# AD9361.net
KiCad netlist of a schematic drawn in Altium Designer
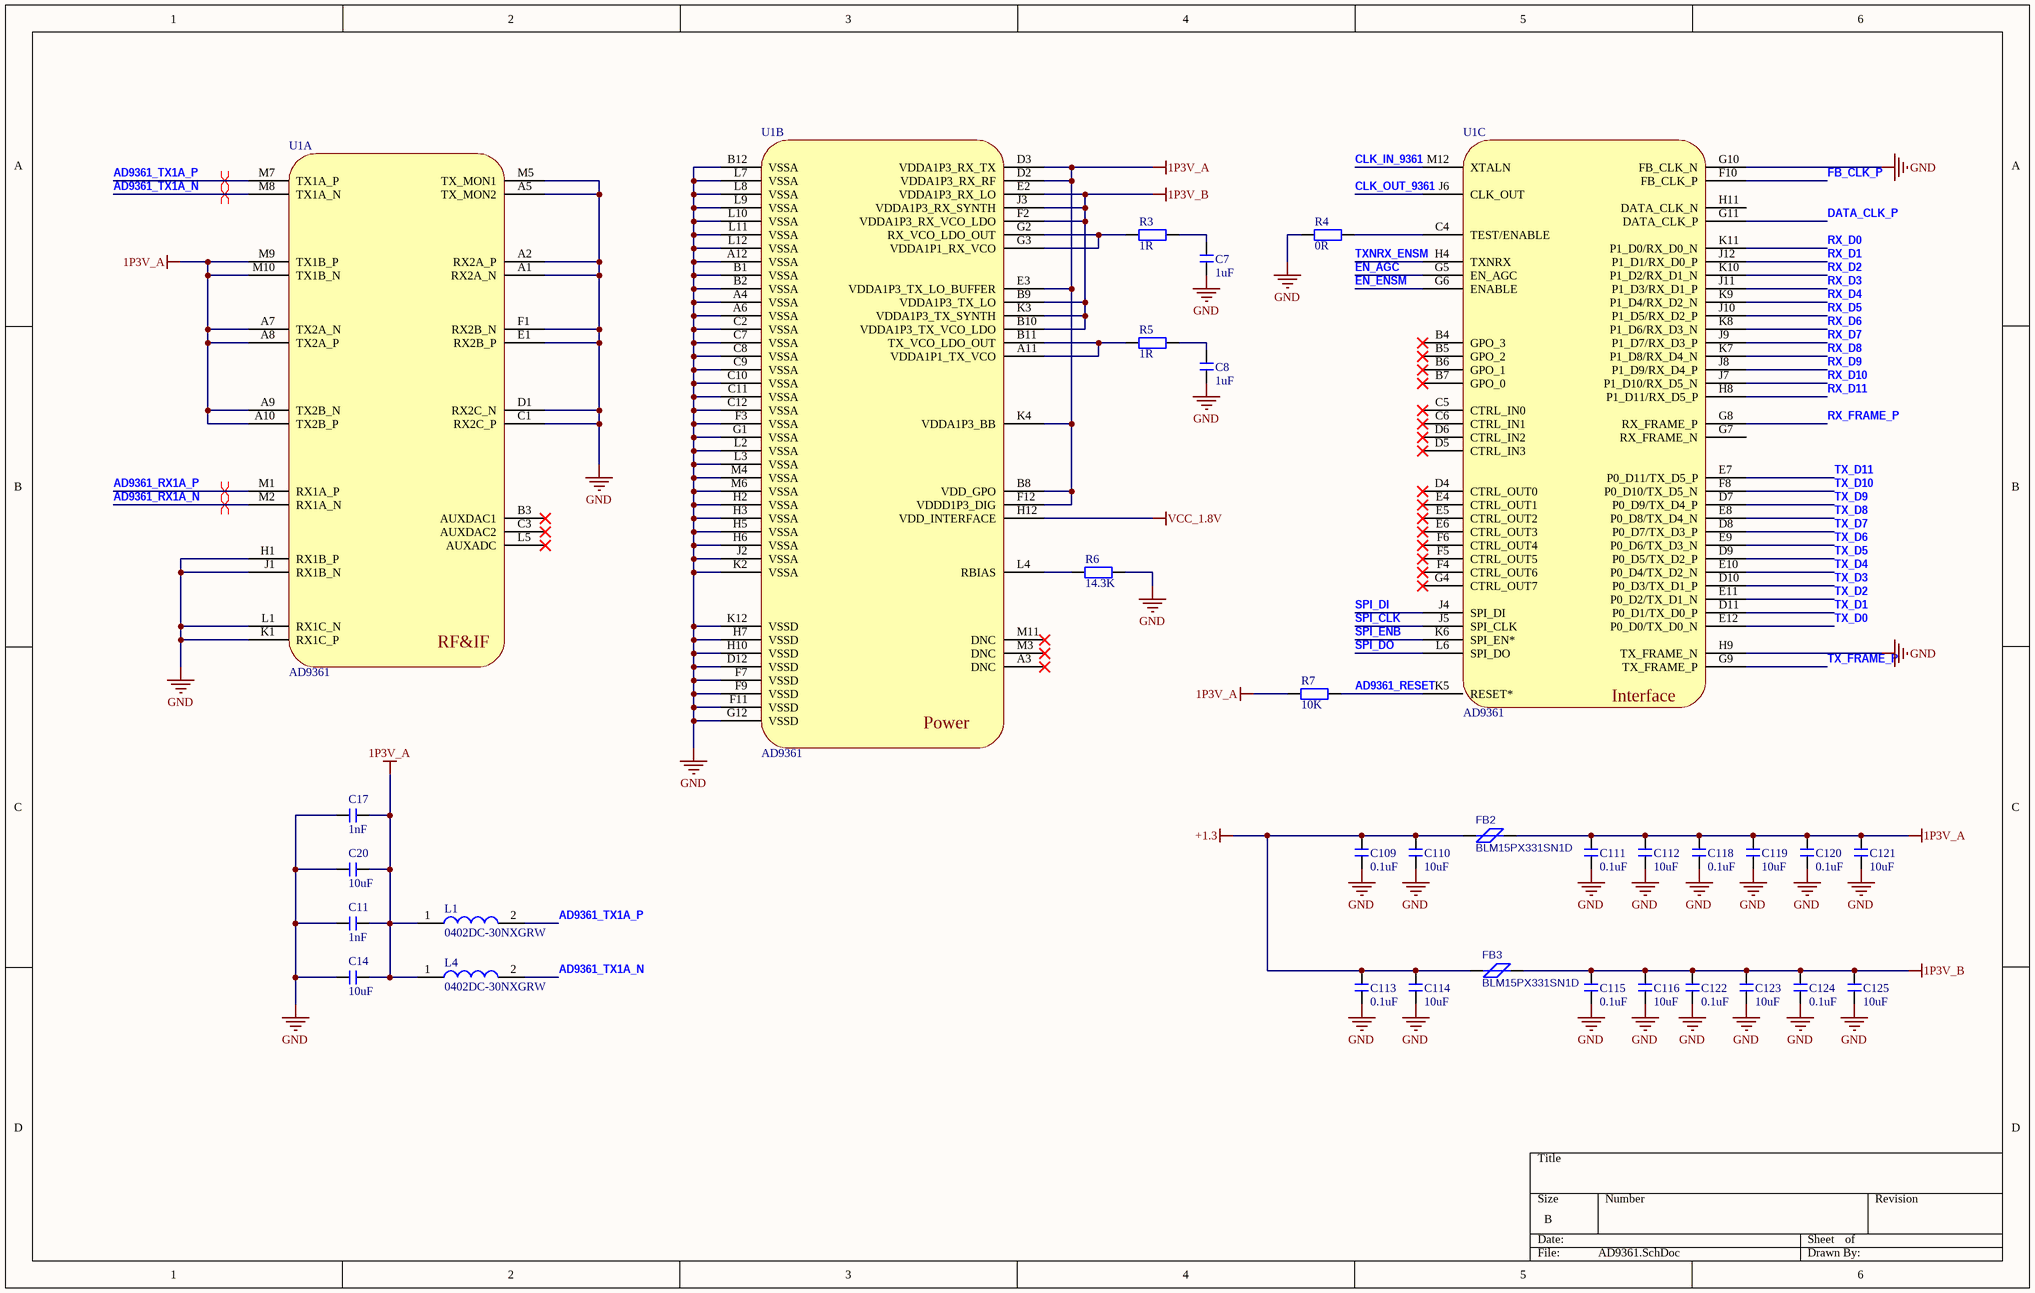
[diagram p0: AD9361.SchDoc]

(export (version "E")
  (design (tool "Eeschema 10.0.6"))
  (components
    (comp (ref "C7")
      (value "1uF")
      (footprint "SamacSys:CAP_0402")
      (description "无极性贴片电容")
      (fields (field (name "版权归属") "源创客"))
      (libsource (lib "源创客") (part "C"))
    )
    (comp (ref "C8")
      (value "1uF")
      (footprint "SamacSys:CAP_0402")
      (description "无极性贴片电容")
      (fields (field (name "版权归属") "源创客"))
      (libsource (lib "源创客") (part "C"))
    )
    (comp (ref "C11")
      (value "1nF")
      (footprint "SamacSys:CAP_0201")
      (description "无极性贴片电容")
      (fields (field (name "版权归属") "源创客"))
      (libsource (lib "源创客") (part "C"))
    )
    (comp (ref "C14")
      (value "10uF")
      (footprint "SamacSys:CAP_0402")
      (description "无极性贴片电容")
      (fields (field (name "版权归属") "源创客"))
      (libsource (lib "源创客") (part "C"))
    )
    (comp (ref "C17")
      (value "1nF")
      (footprint "SamacSys:CAP_0201")
      (description "无极性贴片电容")
      (fields (field (name "版权归属") "源创客"))
      (libsource (lib "源创客") (part "C"))
    )
    (comp (ref "C20")
      (value "10uF")
      (footprint "SamacSys:CAP_0402")
      (description "无极性贴片电容")
      (fields (field (name "版权归属") "源创客"))
      (libsource (lib "源创客") (part "C"))
    )
    (comp (ref "C109")
      (value "0.1uF")
      (footprint "SamacSys:CAP_0402")
      (description "无极性贴片电容")
      (fields (field (name "版权归属") "源创客"))
      (libsource (lib "源创客") (part "C"))
    )
    (comp (ref "C110")
      (value "10uF")
      (footprint "SamacSys:CAP_0402")
      (description "无极性贴片电容")
      (fields (field (name "版权归属") "源创客"))
      (libsource (lib "源创客") (part "C"))
    )
    (comp (ref "C111")
      (value "0.1uF")
      (footprint "SamacSys:CAP_0201")
      (description "无极性贴片电容")
      (fields (field (name "版权归属") "源创客"))
      (libsource (lib "源创客") (part "C"))
    )
    (comp (ref "C112")
      (value "10uF")
      (footprint "SamacSys:CAP_0201")
      (description "无极性贴片电容")
      (fields (field (name "版权归属") "源创客"))
      (libsource (lib "源创客") (part "C"))
    )
    (comp (ref "C113")
      (value "0.1uF")
      (footprint "SamacSys:CAP_0402")
      (description "无极性贴片电容")
      (fields (field (name "版权归属") "源创客"))
      (libsource (lib "源创客") (part "C"))
    )
    (comp (ref "C114")
      (value "10uF")
      (footprint "SamacSys:CAP_0402")
      (description "无极性贴片电容")
      (fields (field (name "版权归属") "源创客"))
      (libsource (lib "源创客") (part "C"))
    )
    (comp (ref "C115")
      (value "0.1uF")
      (footprint "SamacSys:CAP_0201")
      (description "无极性贴片电容")
      (fields (field (name "版权归属") "源创客"))
      (libsource (lib "源创客") (part "C"))
    )
    (comp (ref "C116")
      (value "10uF")
      (footprint "SamacSys:CAP_0201")
      (description "无极性贴片电容")
      (fields (field (name "版权归属") "源创客"))
      (libsource (lib "源创客") (part "C"))
    )
    (comp (ref "C118")
      (value "0.1uF")
      (footprint "SamacSys:CAP_0201")
      (description "无极性贴片电容")
      (fields (field (name "版权归属") "源创客"))
      (libsource (lib "源创客") (part "C"))
    )
    (comp (ref "C119")
      (value "10uF")
      (footprint "SamacSys:CAP_0201")
      (description "无极性贴片电容")
      (fields (field (name "版权归属") "源创客"))
      (libsource (lib "源创客") (part "C"))
    )
    (comp (ref "C120")
      (value "0.1uF")
      (footprint "SamacSys:CAP_0201")
      (description "无极性贴片电容")
      (fields (field (name "版权归属") "源创客"))
      (libsource (lib "源创客") (part "C"))
    )
    (comp (ref "C121")
      (value "10uF")
      (footprint "SamacSys:CAP_0201")
      (description "无极性贴片电容")
      (fields (field (name "版权归属") "源创客"))
      (libsource (lib "源创客") (part "C"))
    )
    (comp (ref "C122")
      (value "0.1uF")
      (footprint "SamacSys:CAP_0201")
      (description "无极性贴片电容")
      (fields (field (name "版权归属") "源创客"))
      (libsource (lib "源创客") (part "C"))
    )
    (comp (ref "C123")
      (value "10uF")
      (footprint "SamacSys:CAP_0201")
      (description "无极性贴片电容")
      (fields (field (name "版权归属") "源创客"))
      (libsource (lib "源创客") (part "C"))
    )
    (comp (ref "C124")
      (value "0.1uF")
      (footprint "SamacSys:CAP_0201")
      (description "无极性贴片电容")
      (fields (field (name "版权归属") "源创客"))
      (libsource (lib "源创客") (part "C"))
    )
    (comp (ref "C125")
      (value "10uF")
      (footprint "SamacSys:CAP_0201")
      (description "无极性贴片电容")
      (fields (field (name "版权归属") "源创客"))
      (libsource (lib "源创客") (part "C"))
    )
    (comp (ref "FB2")
      (value "BLM15PX331SN1D")
      (footprint "0402")
      (fields (field (name "BOM_SUPPLIER PART") "C160975") (field (name "CONTRIBUTOR") "LCSC"))
      (libsource (lib "xc7k160t") (part "BLM15PX331SN1D"))
    )
    (comp (ref "FB3")
      (value "BLM15PX331SN1D")
      (footprint "0402")
      (fields (field (name "BOM_SUPPLIER PART") "C160975") (field (name "CONTRIBUTOR") "LCSC"))
      (libsource (lib "xc7k160t") (part "BLM15PX331SN1D"))
    )
    (comp (ref "L1")
      (value "0402DC-30NXGRW")
      (footprint "0402DC SERIES")
      (description "Inductor")
      (fields
        (field (name "MANUFACTURER_PART_NUMBER") "0402DC-36NXJRW")
        (field (name "MOUSER PART NUMBER") "994-0402DC-36NXJRW")
      )
      (libsource (lib "xc7k160t") (part "0402DC-36NXJRW"))
    )
    (comp (ref "L4")
      (value "0402DC-30NXGRW")
      (footprint "0402DC SERIES")
      (description "Inductor")
      (fields
        (field (name "MANUFACTURER_PART_NUMBER") "0402DC-36NXJRW")
        (field (name "MOUSER PART NUMBER") "994-0402DC-36NXJRW")
      )
      (libsource (lib "xc7k160t") (part "0402DC-36NXJRW"))
    )
    (comp (ref "R3")
      (value "1R")
      (footprint "SamacSys:RES_0201")
      (description "Resistor")
      (libsource (lib "源创客") (part "Resistor"))
    )
    (comp (ref "R4")
      (value "0R")
      (footprint "SamacSys:RES_0201")
      (description "Resistor")
      (libsource (lib "源创客") (part "Resistor"))
    )
    (comp (ref "R5")
      (value "1R")
      (footprint "SamacSys:RES_0201")
      (description "Resistor")
      (libsource (lib "源创客") (part "Resistor"))
    )
    (comp (ref "R6")
      (value "14.3K")
      (footprint "SamacSys:RES_0402")
      (description "Resistor")
      (libsource (lib "源创客") (part "Resistor"))
    )
    (comp (ref "R7")
      (value "10K")
      (footprint "SamacSys:RES_0201")
      (description "Resistor")
      (libsource (lib "源创客") (part "Resistor"))
    )
    (comp (ref "U1") (value "AD9361") (footprint "AD936X") (libsource (lib "xc7k160t") (part "AD9363")))
  )
  (nets
    (net (code "1") (name "+1.3") (class "Default")
      (node (ref "C109") (pin "1") (pinfunction "1_1") (pintype "passive"))
      (node (ref "C110") (pin "2") (pinfunction "2_2") (pintype "passive"))
      (node (ref "C113") (pin "1") (pinfunction "1_1") (pintype "passive"))
      (node (ref "C114") (pin "2") (pinfunction "2_2") (pintype "passive"))
      (node (ref "FB2") (pin "1") (pinfunction "1_1") (pintype "passive"))
      (node (ref "FB3") (pin "1") (pinfunction "1_1") (pintype "passive"))
    )
    (net (code "2") (name "/AD9361_RESET") (class "Default")
      (node (ref "R7") (pin "1") (pinfunction "1_1") (pintype "passive"))
      (node (ref "U1") (pin "K5") (pinfunction "RESET*_K5") (pintype "passive"))
    )
    (net (code "3") (name "/AD9361_RX1A_N") (class "Default")
      (node (ref "U1") (pin "M2") (pinfunction "RX1A_N_M2") (pintype "passive"))
    )
    (net (code "4") (name "/AD9361_RX1A_P") (class "Default")
      (node (ref "U1") (pin "M1") (pinfunction "RX1A_P_M1") (pintype "passive"))
    )
    (net (code "5") (name "/AD9361_TX1A_N") (class "Default")
      (node (ref "L4") (pin "2") (pinfunction "2_2") (pintype "passive"))
      (node (ref "U1") (pin "M8") (pinfunction "TX1A_N_M8") (pintype "passive"))
    )
    (net (code "6") (name "/AD9361_TX1A_P") (class "Default")
      (node (ref "L1") (pin "2") (pinfunction "2_2") (pintype "passive"))
      (node (ref "U1") (pin "M7") (pinfunction "TX1A_P_M7") (pintype "passive"))
    )
    (net (code "7") (name "/CLK_IN_9361") (class "Default")
      (node (ref "U1") (pin "M12") (pinfunction "XTALN_M12") (pintype "passive"))
    )
    (net (code "8") (name "/CLK_OUT_9361") (class "Default")
      (node (ref "U1") (pin "J6") (pinfunction "CLK_OUT_J6") (pintype "passive"))
    )
    (net (code "9") (name "/DATA_CLK_P") (class "Default")
      (node (ref "U1") (pin "G11") (pinfunction "DATA_CLK_P_G11") (pintype "passive"))
    )
    (net (code "10") (name "/EN_AGC") (class "Default")
      (node (ref "U1") (pin "G5") (pinfunction "EN_AGC_G5") (pintype "passive"))
    )
    (net (code "11") (name "/EN_ENSM") (class "Default")
      (node (ref "U1") (pin "G6") (pinfunction "ENABLE_G6") (pintype "passive"))
    )
    (net (code "12") (name "/FB_CLK_P") (class "Default")
      (node (ref "U1") (pin "F10") (pinfunction "FB_CLK_P_F10") (pintype "passive"))
    )
    (net (code "13") (name "/RX_D0") (class "Default")
      (node (ref "U1") (pin "K11") (pinfunction "P1_D0/RX_D0_N_K11") (pintype "passive"))
    )
    (net (code "14") (name "/RX_D1") (class "Default")
      (node (ref "U1") (pin "J12") (pinfunction "P1_D1/RX_D0_P_J12") (pintype "passive"))
    )
    (net (code "15") (name "/RX_D2") (class "Default")
      (node (ref "U1") (pin "K10") (pinfunction "P1_D2/RX_D1_N_K10") (pintype "passive"))
    )
    (net (code "16") (name "/RX_D3") (class "Default")
      (node (ref "U1") (pin "J11") (pinfunction "P1_D3/RX_D1_P_J11") (pintype "passive"))
    )
    (net (code "17") (name "/RX_D4") (class "Default")
      (node (ref "U1") (pin "K9") (pinfunction "P1_D4/RX_D2_N_K9") (pintype "passive"))
    )
    (net (code "18") (name "/RX_D5") (class "Default")
      (node (ref "U1") (pin "J10") (pinfunction "P1_D5/RX_D2_P_J10") (pintype "passive"))
    )
    (net (code "19") (name "/RX_D6") (class "Default")
      (node (ref "U1") (pin "K8") (pinfunction "P1_D6/RX_D3_N_K8") (pintype "passive"))
    )
    (net (code "20") (name "/RX_D7") (class "Default")
      (node (ref "U1") (pin "J9") (pinfunction "P1_D7/RX_D3_P_J9") (pintype "passive"))
    )
    (net (code "21") (name "/RX_D8") (class "Default")
      (node (ref "U1") (pin "K7") (pinfunction "P1_D8/RX_D4_N_K7") (pintype "passive"))
    )
    (net (code "22") (name "/RX_D9") (class "Default")
      (node (ref "U1") (pin "J8") (pinfunction "P1_D9/RX_D4_P_J8") (pintype "passive"))
    )
    (net (code "23") (name "/RX_D10") (class "Default")
      (node (ref "U1") (pin "J7") (pinfunction "P1_D10/RX_D5_N_J7") (pintype "passive"))
    )
    (net (code "24") (name "/RX_D11") (class "Default")
      (node (ref "U1") (pin "H8") (pinfunction "P1_D11/RX_D5_P_H8") (pintype "passive"))
    )
    (net (code "25") (name "/RX_FRAME_P") (class "Default")
      (node (ref "U1") (pin "G8") (pinfunction "RX_FRAME_P_G8") (pintype "passive"))
    )
    (net (code "26") (name "/SPI_CLK") (class "Default")
      (node (ref "U1") (pin "J5") (pinfunction "SPI_CLK_J5") (pintype "passive"))
    )
    (net (code "27") (name "/SPI_DI") (class "Default")
      (node (ref "U1") (pin "J4") (pinfunction "SPI_DI_J4") (pintype "passive"))
    )
    (net (code "28") (name "/SPI_DO") (class "Default")
      (node (ref "U1") (pin "L6") (pinfunction "SPI_DO_L6") (pintype "passive"))
    )
    (net (code "29") (name "/SPI_ENB") (class "Default")
      (node (ref "U1") (pin "K6") (pinfunction "SPI_EN*_K6") (pintype "passive"))
    )
    (net (code "30") (name "/TXNRX_ENSM") (class "Default")
      (node (ref "U1") (pin "H4") (pinfunction "TXNRX_H4") (pintype "passive"))
    )
    (net (code "31") (name "/TX_D0") (class "Default")
      (node (ref "U1") (pin "E12") (pinfunction "P0_D0/TX_D0_N_E12") (pintype "passive"))
    )
    (net (code "32") (name "/TX_D1") (class "Default")
      (node (ref "U1") (pin "D11") (pinfunction "P0_D1/TX_D0_P_D11") (pintype "passive"))
    )
    (net (code "33") (name "/TX_D2") (class "Default")
      (node (ref "U1") (pin "E11") (pinfunction "P0_D2/TX_D1_N_E11") (pintype "passive"))
    )
    (net (code "34") (name "/TX_D3") (class "Default")
      (node (ref "U1") (pin "D10") (pinfunction "P0_D3/TX_D1_P_D10") (pintype "passive"))
    )
    (net (code "35") (name "/TX_D4") (class "Default")
      (node (ref "U1") (pin "E10") (pinfunction "P0_D4/TX_D2_N_E10") (pintype "passive"))
    )
    (net (code "36") (name "/TX_D5") (class "Default")
      (node (ref "U1") (pin "D9") (pinfunction "P0_D5/TX_D2_P_D9") (pintype "passive"))
    )
    (net (code "37") (name "/TX_D6") (class "Default")
      (node (ref "U1") (pin "E9") (pinfunction "P0_D6/TX_D3_N_E9") (pintype "passive"))
    )
    (net (code "38") (name "/TX_D7") (class "Default")
      (node (ref "U1") (pin "D8") (pinfunction "P0_D7/TX_D3_P_D8") (pintype "passive"))
    )
    (net (code "39") (name "/TX_D8") (class "Default")
      (node (ref "U1") (pin "E8") (pinfunction "P0_D8/TX_D4_N_E8") (pintype "passive"))
    )
    (net (code "40") (name "/TX_D9") (class "Default")
      (node (ref "U1") (pin "D7") (pinfunction "P0_D9/TX_D4_P_D7") (pintype "passive"))
    )
    (net (code "41") (name "/TX_D10") (class "Default")
      (node (ref "U1") (pin "F8") (pinfunction "P0_D10/TX_D5_N_F8") (pintype "passive"))
    )
    (net (code "42") (name "/TX_D11") (class "Default")
      (node (ref "U1") (pin "E7") (pinfunction "P0_D11/TX_D5_P_E7") (pintype "passive"))
    )
    (net (code "43") (name "/TX_FRAME_P") (class "Default")
      (node (ref "U1") (pin "G9") (pinfunction "TX_FRAME_P_G9") (pintype "passive"))
    )
    (net (code "44") (name "1P3V_A") (class "Default")
      (node (ref "C11") (pin "2") (pinfunction "2_2") (pintype "passive"))
      (node (ref "C111") (pin "1") (pinfunction "1_1") (pintype "passive"))
      (node (ref "C112") (pin "2") (pinfunction "2_2") (pintype "passive"))
      (node (ref "C118") (pin "1") (pinfunction "1_1") (pintype "passive"))
      (node (ref "C119") (pin "2") (pinfunction "2_2") (pintype "passive"))
      (node (ref "C120") (pin "1") (pinfunction "1_1") (pintype "passive"))
      (node (ref "C121") (pin "2") (pinfunction "2_2") (pintype "passive"))
      (node (ref "C14") (pin "2") (pinfunction "2_2") (pintype "passive"))
      (node (ref "C17") (pin "2") (pinfunction "2_2") (pintype "passive"))
      (node (ref "C20") (pin "2") (pinfunction "2_2") (pintype "passive"))
      (node (ref "FB2") (pin "2") (pinfunction "2_2") (pintype "passive"))
      (node (ref "L1") (pin "1") (pinfunction "1_1") (pintype "passive"))
      (node (ref "L4") (pin "1") (pinfunction "1_1") (pintype "passive"))
      (node (ref "R7") (pin "2") (pinfunction "2_2") (pintype "passive"))
      (node (ref "U1") (pin "A10") (pinfunction "TX2B_P_A10") (pintype "passive"))
      (node (ref "U1") (pin "A7") (pinfunction "TX2A_N_A7") (pintype "passive"))
      (node (ref "U1") (pin "A8") (pinfunction "TX2A_P_A8") (pintype "passive"))
      (node (ref "U1") (pin "A9") (pinfunction "TX2B_N_A9") (pintype "passive"))
      (node (ref "U1") (pin "B8") (pinfunction "VDD_GPO_B8") (pintype "passive"))
      (node (ref "U1") (pin "D2") (pinfunction "VDDA1P3_RX_RF_D2") (pintype "passive"))
      (node (ref "U1") (pin "D3") (pinfunction "VDDA1P3_RX_TX_D3") (pintype "passive"))
      (node (ref "U1") (pin "E3") (pinfunction "VDDA1P3_TX_LO_BUFFER_E3") (pintype "passive"))
      (node (ref "U1") (pin "F12") (pinfunction "VDDD1P3_DIG_F12") (pintype "passive"))
      (node (ref "U1") (pin "K4") (pinfunction "VDDA1P3_BB_K4") (pintype "passive"))
      (node (ref "U1") (pin "M10") (pinfunction "TX1B_N_M10") (pintype "passive"))
      (node (ref "U1") (pin "M9") (pinfunction "TX1B_P_M9") (pintype "passive"))
    )
    (net (code "45") (name "1P3V_B") (class "Default")
      (node (ref "C115") (pin "1") (pinfunction "1_1") (pintype "passive"))
      (node (ref "C116") (pin "2") (pinfunction "2_2") (pintype "passive"))
      (node (ref "C122") (pin "1") (pinfunction "1_1") (pintype "passive"))
      (node (ref "C123") (pin "2") (pinfunction "2_2") (pintype "passive"))
      (node (ref "C124") (pin "1") (pinfunction "1_1") (pintype "passive"))
      (node (ref "C125") (pin "2") (pinfunction "2_2") (pintype "passive"))
      (node (ref "FB3") (pin "2") (pinfunction "2_2") (pintype "passive"))
      (node (ref "U1") (pin "B10") (pinfunction "VDDA1P3_TX_VCO_LDO_B10") (pintype "passive"))
      (node (ref "U1") (pin "B9") (pinfunction "VDDA1P3_TX_LO_B9") (pintype "passive"))
      (node (ref "U1") (pin "E2") (pinfunction "VDDA1P3_RX_LO_E2") (pintype "passive"))
      (node (ref "U1") (pin "F2") (pinfunction "VDDA1P3_RX_VCO_LDO_F2") (pintype "passive"))
      (node (ref "U1") (pin "J3") (pinfunction "VDDA1P3_RX_SYNTH_J3") (pintype "passive"))
      (node (ref "U1") (pin "K3") (pinfunction "VDDA1P3_TX_SYNTH_K3") (pintype "passive"))
    )
    (net (code "46") (name "GND") (class "Default")
      (node (ref "C109") (pin "2") (pinfunction "2_2") (pintype "passive"))
      (node (ref "C11") (pin "1") (pinfunction "1_1") (pintype "passive"))
      (node (ref "C110") (pin "1") (pinfunction "1_1") (pintype "passive"))
      (node (ref "C111") (pin "2") (pinfunction "2_2") (pintype "passive"))
      (node (ref "C112") (pin "1") (pinfunction "1_1") (pintype "passive"))
      (node (ref "C113") (pin "2") (pinfunction "2_2") (pintype "passive"))
      (node (ref "C114") (pin "1") (pinfunction "1_1") (pintype "passive"))
      (node (ref "C115") (pin "2") (pinfunction "2_2") (pintype "passive"))
      (node (ref "C116") (pin "1") (pinfunction "1_1") (pintype "passive"))
      (node (ref "C118") (pin "2") (pinfunction "2_2") (pintype "passive"))
      (node (ref "C119") (pin "1") (pinfunction "1_1") (pintype "passive"))
      (node (ref "C120") (pin "2") (pinfunction "2_2") (pintype "passive"))
      (node (ref "C121") (pin "1") (pinfunction "1_1") (pintype "passive"))
      (node (ref "C122") (pin "2") (pinfunction "2_2") (pintype "passive"))
      (node (ref "C123") (pin "1") (pinfunction "1_1") (pintype "passive"))
      (node (ref "C124") (pin "2") (pinfunction "2_2") (pintype "passive"))
      (node (ref "C125") (pin "1") (pinfunction "1_1") (pintype "passive"))
      (node (ref "C14") (pin "1") (pinfunction "1_1") (pintype "passive"))
      (node (ref "C17") (pin "1") (pinfunction "1_1") (pintype "passive"))
      (node (ref "C20") (pin "1") (pinfunction "1_1") (pintype "passive"))
      (node (ref "C7") (pin "1") (pinfunction "1_1") (pintype "passive"))
      (node (ref "C8") (pin "1") (pinfunction "1_1") (pintype "passive"))
      (node (ref "R4") (pin "2") (pinfunction "2_2") (pintype "passive"))
      (node (ref "R6") (pin "1") (pinfunction "1_1") (pintype "passive"))
      (node (ref "U1") (pin "A1") (pinfunction "RX2A_N_A1") (pintype "passive"))
      (node (ref "U1") (pin "A12") (pinfunction "VSSA_A12") (pintype "passive"))
      (node (ref "U1") (pin "A2") (pinfunction "RX2A_P_A2") (pintype "passive"))
      (node (ref "U1") (pin "A4") (pinfunction "VSSA_A4") (pintype "passive"))
      (node (ref "U1") (pin "A5") (pinfunction "TX_MON2_A5") (pintype "passive"))
      (node (ref "U1") (pin "A6") (pinfunction "VSSA_A6") (pintype "passive"))
      (node (ref "U1") (pin "B1") (pinfunction "VSSA_B1") (pintype "passive"))
      (node (ref "U1") (pin "B12") (pinfunction "VSSA_B12") (pintype "passive"))
      (node (ref "U1") (pin "B2") (pinfunction "VSSA_B2") (pintype "passive"))
      (node (ref "U1") (pin "C1") (pinfunction "RX2C_P_C1") (pintype "passive"))
      (node (ref "U1") (pin "C10") (pinfunction "VSSA_C10") (pintype "passive"))
      (node (ref "U1") (pin "C11") (pinfunction "VSSA_C11") (pintype "passive"))
      (node (ref "U1") (pin "C12") (pinfunction "VSSA_C12") (pintype "passive"))
      (node (ref "U1") (pin "C2") (pinfunction "VSSA_C2") (pintype "passive"))
      (node (ref "U1") (pin "C7") (pinfunction "VSSA_C7") (pintype "passive"))
      (node (ref "U1") (pin "C8") (pinfunction "VSSA_C8") (pintype "passive"))
      (node (ref "U1") (pin "C9") (pinfunction "VSSA_C9") (pintype "passive"))
      (node (ref "U1") (pin "D1") (pinfunction "RX2C_N_D1") (pintype "passive"))
      (node (ref "U1") (pin "D12") (pinfunction "VSSD_D12") (pintype "passive"))
      (node (ref "U1") (pin "E1") (pinfunction "RX2B_P_E1") (pintype "passive"))
      (node (ref "U1") (pin "F1") (pinfunction "RX2B_N_F1") (pintype "passive"))
      (node (ref "U1") (pin "F11") (pinfunction "VSSD_F11") (pintype "passive"))
      (node (ref "U1") (pin "F3") (pinfunction "VSSA_F3") (pintype "passive"))
      (node (ref "U1") (pin "F7") (pinfunction "VSSD_F7") (pintype "passive"))
      (node (ref "U1") (pin "F9") (pinfunction "VSSD_F9") (pintype "passive"))
      (node (ref "U1") (pin "G1") (pinfunction "VSSA_G1") (pintype "passive"))
      (node (ref "U1") (pin "G10") (pinfunction "FB_CLK_N_G10") (pintype "passive"))
      (node (ref "U1") (pin "G12") (pinfunction "VSSD_G12") (pintype "passive"))
      (node (ref "U1") (pin "H1") (pinfunction "RX1B_P_H1") (pintype "passive"))
      (node (ref "U1") (pin "H10") (pinfunction "VSSD_H10") (pintype "passive"))
      (node (ref "U1") (pin "H2") (pinfunction "VSSA_H2") (pintype "passive"))
      (node (ref "U1") (pin "H3") (pinfunction "VSSA_H3") (pintype "passive"))
      (node (ref "U1") (pin "H5") (pinfunction "VSSA_H5") (pintype "passive"))
      (node (ref "U1") (pin "H6") (pinfunction "VSSA_H6") (pintype "passive"))
      (node (ref "U1") (pin "H7") (pinfunction "VSSD_H7") (pintype "passive"))
      (node (ref "U1") (pin "H9") (pinfunction "TX_FRAME_N_H9") (pintype "passive"))
      (node (ref "U1") (pin "J1") (pinfunction "RX1B_N_J1") (pintype "passive"))
      (node (ref "U1") (pin "J2") (pinfunction "VSSA_J2") (pintype "passive"))
      (node (ref "U1") (pin "K1") (pinfunction "RX1C_P_K1") (pintype "passive"))
      (node (ref "U1") (pin "K12") (pinfunction "VSSD_K12") (pintype "passive"))
      (node (ref "U1") (pin "K2") (pinfunction "VSSA_K2") (pintype "passive"))
      (node (ref "U1") (pin "L1") (pinfunction "RX1C_N_L1") (pintype "passive"))
      (node (ref "U1") (pin "L10") (pinfunction "VSSA_L10") (pintype "passive"))
      (node (ref "U1") (pin "L11") (pinfunction "VSSA_L11") (pintype "passive"))
      (node (ref "U1") (pin "L12") (pinfunction "VSSA_L12") (pintype "passive"))
      (node (ref "U1") (pin "L2") (pinfunction "VSSA_L2") (pintype "passive"))
      (node (ref "U1") (pin "L3") (pinfunction "VSSA_L3") (pintype "passive"))
      (node (ref "U1") (pin "L7") (pinfunction "VSSA_L7") (pintype "passive"))
      (node (ref "U1") (pin "L8") (pinfunction "VSSA_L8") (pintype "passive"))
      (node (ref "U1") (pin "L9") (pinfunction "VSSA_L9") (pintype "passive"))
      (node (ref "U1") (pin "M4") (pinfunction "VSSA_M4") (pintype "passive"))
      (node (ref "U1") (pin "M5") (pinfunction "TX_MON1_M5") (pintype "passive"))
      (node (ref "U1") (pin "M6") (pinfunction "VSSA_M6") (pintype "passive"))
    )
    (net (code "47") (name "Net-(C7-Pad2)") (class "Default")
      (node (ref "C7") (pin "2") (pinfunction "2_2") (pintype "passive"))
      (node (ref "R3") (pin "1") (pinfunction "1_1") (pintype "passive"))
    )
    (net (code "48") (name "Net-(C8-Pad2)") (class "Default")
      (node (ref "C8") (pin "2") (pinfunction "2_2") (pintype "passive"))
      (node (ref "R5") (pin "1") (pinfunction "1_1") (pintype "passive"))
    )
    (net (code "49") (name "Net-(U1B-RBIAS)") (class "Default")
      (node (ref "R6") (pin "2") (pinfunction "2_2") (pintype "passive"))
      (node (ref "U1") (pin "L4") (pinfunction "RBIAS_L4") (pintype "passive"))
    )
    (net (code "50") (name "Net-(U1B-RX_VCO_LDO_OUT)") (class "Default")
      (node (ref "R3") (pin "2") (pinfunction "2_2") (pintype "passive"))
      (node (ref "U1") (pin "G2") (pinfunction "RX_VCO_LDO_OUT_G2") (pintype "passive"))
      (node (ref "U1") (pin "G3") (pinfunction "VDDA1P1_RX_VCO_G3") (pintype "passive"))
    )
    (net (code "51") (name "Net-(U1B-TX_VCO_LDO_OUT)") (class "Default")
      (node (ref "R5") (pin "2") (pinfunction "2_2") (pintype "passive"))
      (node (ref "U1") (pin "A11") (pinfunction "VDDA1P1_TX_VCO_A11") (pintype "passive"))
      (node (ref "U1") (pin "B11") (pinfunction "TX_VCO_LDO_OUT_B11") (pintype "passive"))
    )
    (net (code "52") (name "Net-(U1C-TEST{slash}ENABLE)") (class "Default")
      (node (ref "R4") (pin "1") (pinfunction "1_1") (pintype "passive"))
      (node (ref "U1") (pin "C4") (pinfunction "TEST/ENABLE_C4") (pintype "passive"))
    )
    (net (code "53") (name "VCC_1.8V") (class "Default")
      (node (ref "U1") (pin "H12") (pinfunction "VDD_INTERFACE_H12") (pintype "passive"))
    )
    (net (code "54") (name "unconnected-(U1A-AUXADC-PadL5)") (class "Default")
      (node (ref "U1") (pin "L5") (pinfunction "AUXADC_L5") (pintype "passive+no_connect"))
    )
    (net (code "55") (name "unconnected-(U1A-AUXDAC1-PadB3)") (class "Default")
      (node (ref "U1") (pin "B3") (pinfunction "AUXDAC1_B3") (pintype "passive+no_connect"))
    )
    (net (code "56") (name "unconnected-(U1A-AUXDAC2-PadC3)") (class "Default")
      (node (ref "U1") (pin "C3") (pinfunction "AUXDAC2_C3") (pintype "passive+no_connect"))
    )
    (net (code "57") (name "unconnected-(U1B-DNC-PadA3)") (class "Default")
      (node (ref "U1") (pin "A3") (pinfunction "DNC_A3") (pintype "passive+no_connect"))
    )
    (net (code "58") (name "unconnected-(U1B-DNC-PadM3)") (class "Default")
      (node (ref "U1") (pin "M3") (pinfunction "DNC_M3") (pintype "passive+no_connect"))
    )
    (net (code "59") (name "unconnected-(U1B-DNC-PadM11)") (class "Default")
      (node (ref "U1") (pin "M11") (pinfunction "DNC_M11") (pintype "passive+no_connect"))
    )
    (net (code "60") (name "unconnected-(U1C-CTRL_IN0-PadC5)") (class "Default")
      (node (ref "U1") (pin "C5") (pinfunction "CTRL_IN0_C5") (pintype "passive+no_connect"))
    )
    (net (code "61") (name "unconnected-(U1C-CTRL_IN1-PadC6)") (class "Default")
      (node (ref "U1") (pin "C6") (pinfunction "CTRL_IN1_C6") (pintype "passive+no_connect"))
    )
    (net (code "62") (name "unconnected-(U1C-CTRL_IN2-PadD6)") (class "Default")
      (node (ref "U1") (pin "D6") (pinfunction "CTRL_IN2_D6") (pintype "passive+no_connect"))
    )
    (net (code "63") (name "unconnected-(U1C-CTRL_IN3-PadD5)") (class "Default")
      (node (ref "U1") (pin "D5") (pinfunction "CTRL_IN3_D5") (pintype "passive+no_connect"))
    )
    (net (code "64") (name "unconnected-(U1C-CTRL_OUT0-PadD4)") (class "Default")
      (node (ref "U1") (pin "D4") (pinfunction "CTRL_OUT0_D4") (pintype "passive+no_connect"))
    )
    (net (code "65") (name "unconnected-(U1C-CTRL_OUT1-PadE4)") (class "Default")
      (node (ref "U1") (pin "E4") (pinfunction "CTRL_OUT1_E4") (pintype "passive+no_connect"))
    )
    (net (code "66") (name "unconnected-(U1C-CTRL_OUT2-PadE5)") (class "Default")
      (node (ref "U1") (pin "E5") (pinfunction "CTRL_OUT2_E5") (pintype "passive+no_connect"))
    )
    (net (code "67") (name "unconnected-(U1C-CTRL_OUT3-PadE6)") (class "Default")
      (node (ref "U1") (pin "E6") (pinfunction "CTRL_OUT3_E6") (pintype "passive+no_connect"))
    )
    (net (code "68") (name "unconnected-(U1C-CTRL_OUT4-PadF6)") (class "Default")
      (node (ref "U1") (pin "F6") (pinfunction "CTRL_OUT4_F6") (pintype "passive+no_connect"))
    )
    (net (code "69") (name "unconnected-(U1C-CTRL_OUT5-PadF5)") (class "Default")
      (node (ref "U1") (pin "F5") (pinfunction "CTRL_OUT5_F5") (pintype "passive+no_connect"))
    )
    (net (code "70") (name "unconnected-(U1C-CTRL_OUT6-PadF4)") (class "Default")
      (node (ref "U1") (pin "F4") (pinfunction "CTRL_OUT6_F4") (pintype "passive+no_connect"))
    )
    (net (code "71") (name "unconnected-(U1C-CTRL_OUT7-PadG4)") (class "Default")
      (node (ref "U1") (pin "G4") (pinfunction "CTRL_OUT7_G4") (pintype "passive+no_connect"))
    )
    (net (code "72") (name "unconnected-(U1C-DATA_CLK_N-PadH11)") (class "Default")
      (node (ref "U1") (pin "H11") (pinfunction "DATA_CLK_N_H11") (pintype "passive"))
    )
    (net (code "73") (name "unconnected-(U1C-GPO_0-PadB7)") (class "Default")
      (node (ref "U1") (pin "B7") (pinfunction "GPO_0_B7") (pintype "passive+no_connect"))
    )
    (net (code "74") (name "unconnected-(U1C-GPO_1-PadB6)") (class "Default")
      (node (ref "U1") (pin "B6") (pinfunction "GPO_1_B6") (pintype "passive+no_connect"))
    )
    (net (code "75") (name "unconnected-(U1C-GPO_2-PadB5)") (class "Default")
      (node (ref "U1") (pin "B5") (pinfunction "GPO_2_B5") (pintype "passive+no_connect"))
    )
    (net (code "76") (name "unconnected-(U1C-GPO_3-PadB4)") (class "Default")
      (node (ref "U1") (pin "B4") (pinfunction "GPO_3_B4") (pintype "passive+no_connect"))
    )
    (net (code "77") (name "unconnected-(U1C-RX_FRAME_N-PadG7)") (class "Default")
      (node (ref "U1") (pin "G7") (pinfunction "RX_FRAME_N_G7") (pintype "passive"))
    )
  )
)
